# analog_part.net
KiCad netlist of a schematic drawn in Altium Designer
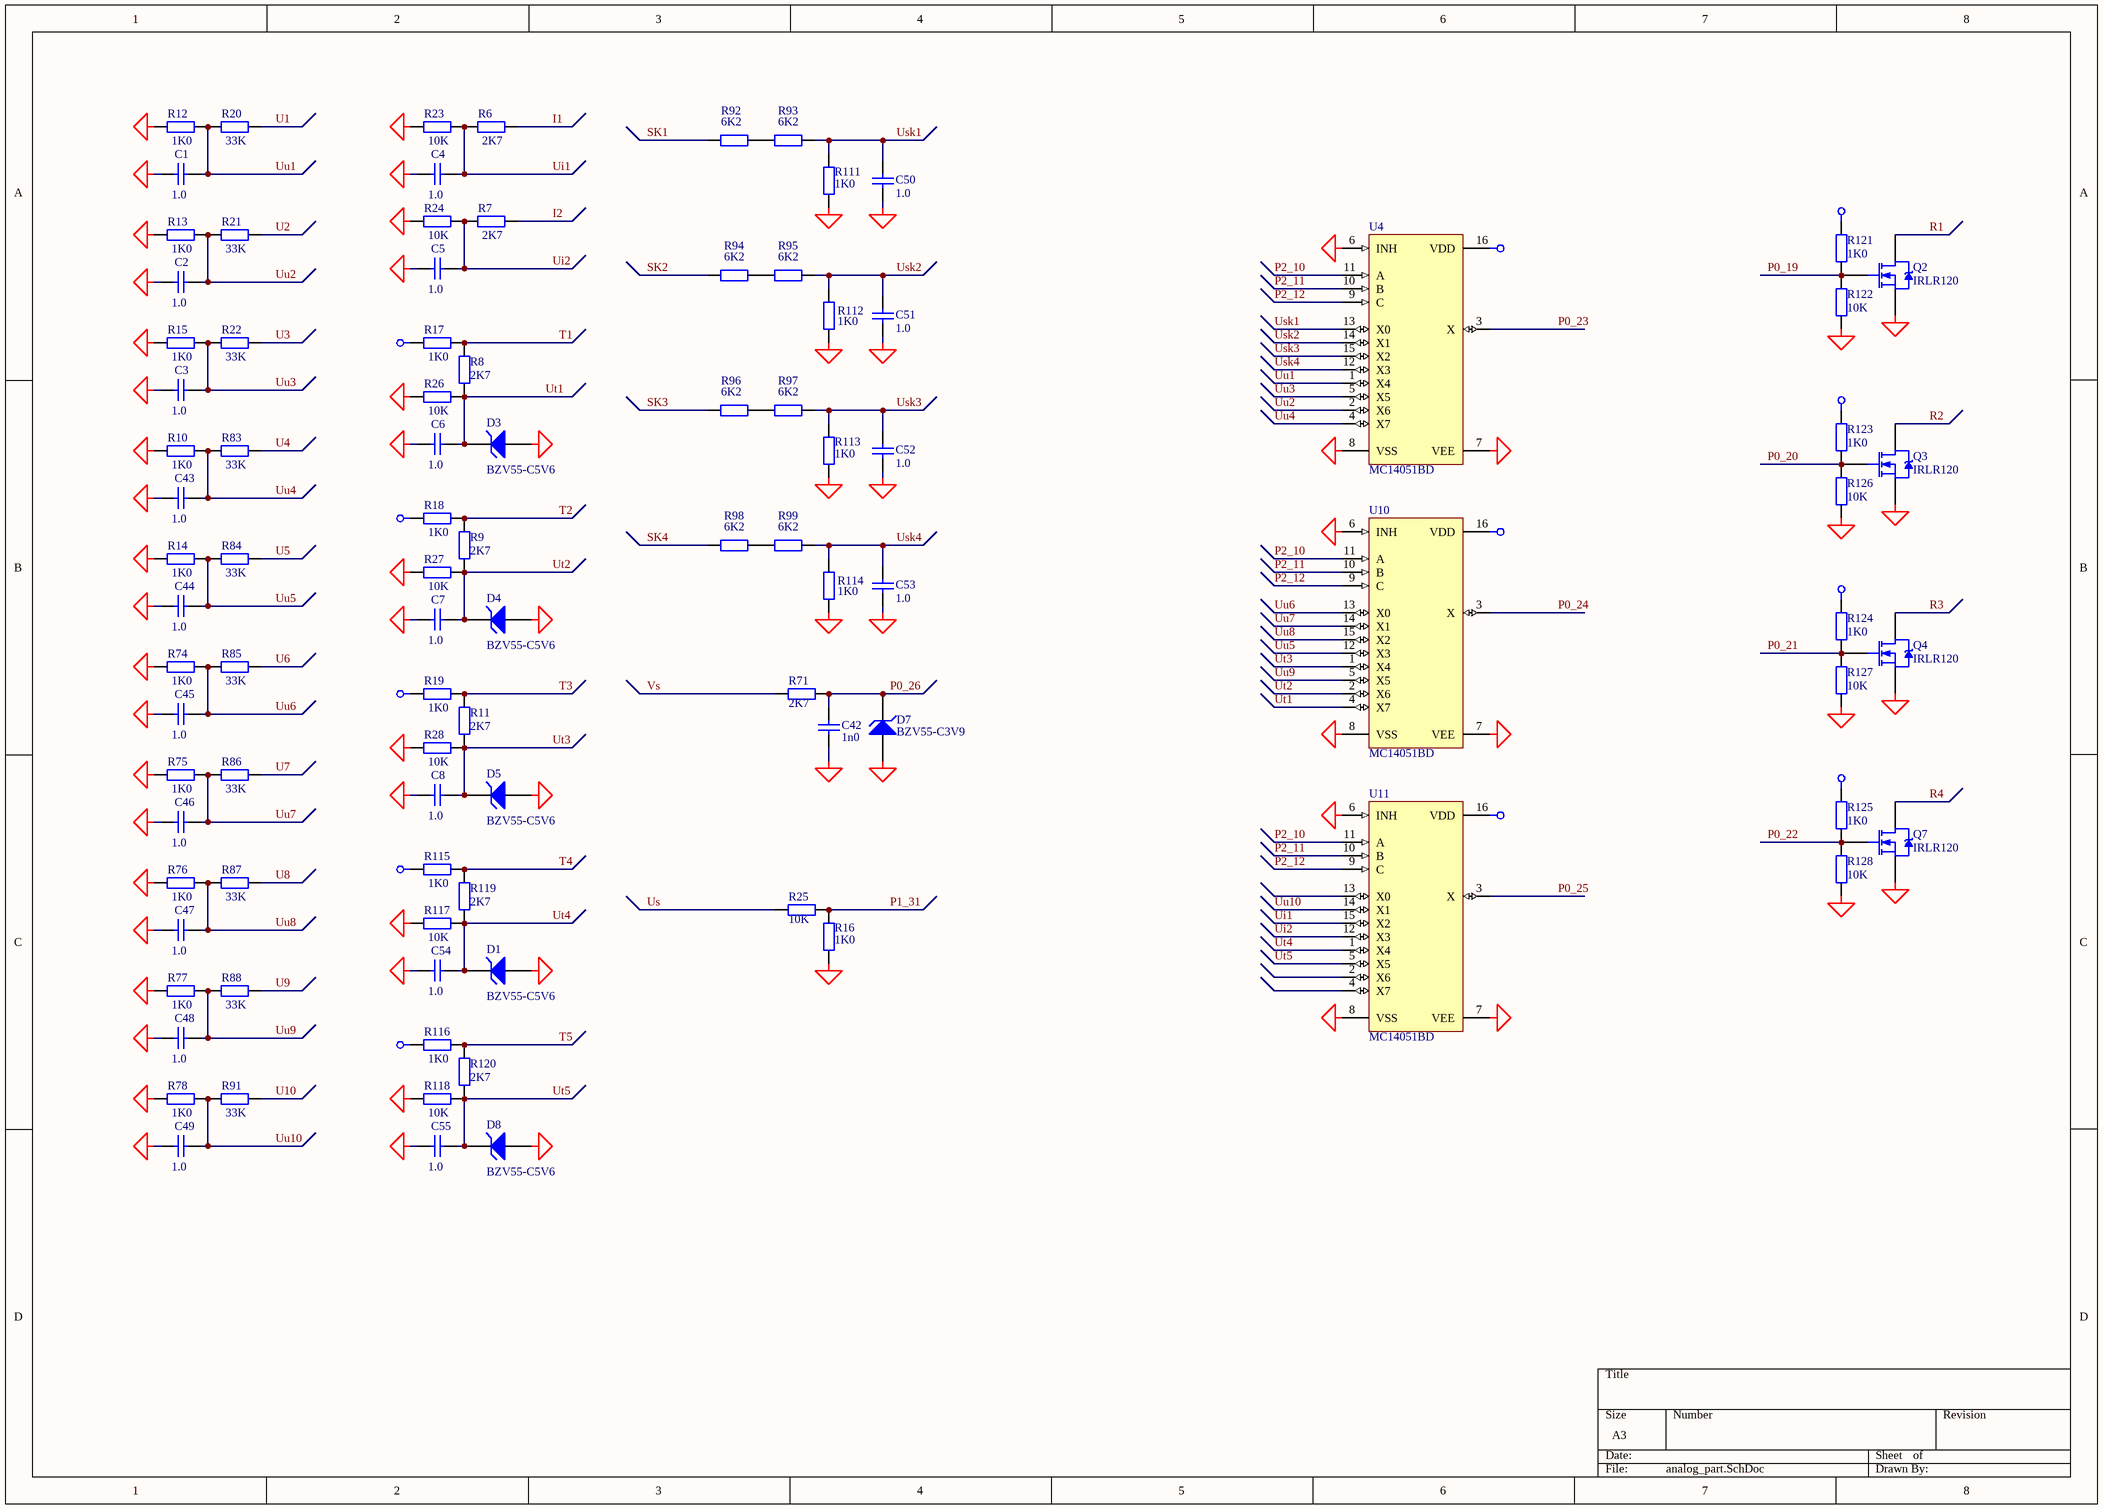
[diagram p0: analog_part.SchDoc]

(export (version "E")
  (design (tool "Eeschema 10.0.6"))
  (components
    (comp (ref "C1")
      (value "1.0")
      (footprint "C3216-1206")
      (description "Capacitor (Semiconductor SIM Model)")
      (fields (field (name "MANUFACTURER") "Generic Components") (field (name "PUBLISHER") "Altium Limited"))
      (libsource (lib "Miscellaneous Devices") (part "Cap Semi"))
    )
    (comp (ref "C2")
      (value "1.0")
      (footprint "C3216-1206")
      (description "Capacitor (Semiconductor SIM Model)")
      (fields (field (name "MANUFACTURER") "Generic Components") (field (name "PUBLISHER") "Altium Limited"))
      (libsource (lib "Miscellaneous Devices") (part "Cap Semi"))
    )
    (comp (ref "C3")
      (value "1.0")
      (footprint "C3216-1206")
      (description "Capacitor (Semiconductor SIM Model)")
      (fields (field (name "MANUFACTURER") "Generic Components") (field (name "PUBLISHER") "Altium Limited"))
      (libsource (lib "Miscellaneous Devices") (part "Cap Semi"))
    )
    (comp (ref "C4")
      (value "1.0")
      (footprint "C3216-1206")
      (description "Capacitor (Semiconductor SIM Model)")
      (fields (field (name "MANUFACTURER") "Generic Components") (field (name "PUBLISHER") "Altium Limited"))
      (libsource (lib "Miscellaneous Devices") (part "Cap Semi"))
    )
    (comp (ref "C5")
      (value "1.0")
      (footprint "C3216-1206")
      (description "Capacitor (Semiconductor SIM Model)")
      (fields (field (name "MANUFACTURER") "Generic Components") (field (name "PUBLISHER") "Altium Limited"))
      (libsource (lib "Miscellaneous Devices") (part "Cap Semi"))
    )
    (comp (ref "C6")
      (value "1.0")
      (footprint "C3216-1206")
      (description "Capacitor (Semiconductor SIM Model)")
      (fields (field (name "MANUFACTURER") "Generic Components") (field (name "PUBLISHER") "Altium Limited"))
      (libsource (lib "Miscellaneous Devices") (part "Cap Semi"))
    )
    (comp (ref "C7")
      (value "1.0")
      (footprint "C3216-1206")
      (description "Capacitor (Semiconductor SIM Model)")
      (fields (field (name "MANUFACTURER") "Generic Components") (field (name "PUBLISHER") "Altium Limited"))
      (libsource (lib "Miscellaneous Devices") (part "Cap Semi"))
    )
    (comp (ref "C8")
      (value "1.0")
      (footprint "_1206")
      (description "Capacitor (Semiconductor SIM Model)")
      (fields (field (name "MANUFACTURER") "Generic Components") (field (name "PUBLISHER") "Altium Limited"))
      (libsource (lib "Miscellaneous Devices") (part "Cap Semi"))
    )
    (comp (ref "C42")
      (value "1n0")
      (footprint "_1206")
      (description "Capacitor (Semiconductor SIM Model)")
      (fields (field (name "MANUFACTURER") "Generic Components") (field (name "PUBLISHER") "Altium Limited"))
      (libsource (lib "") (part "Cap Semi_1"))
    )
    (comp (ref "C43")
      (value "1.0")
      (footprint "C3216-1206")
      (description "Capacitor (Semiconductor SIM Model)")
      (fields (field (name "MANUFACTURER") "Generic Components") (field (name "PUBLISHER") "Altium Limited"))
      (libsource (lib "Miscellaneous Devices") (part "Cap Semi"))
    )
    (comp (ref "C44")
      (value "1.0")
      (footprint "C3216-1206")
      (description "Capacitor (Semiconductor SIM Model)")
      (fields (field (name "MANUFACTURER") "Generic Components") (field (name "PUBLISHER") "Altium Limited"))
      (libsource (lib "Miscellaneous Devices") (part "Cap Semi"))
    )
    (comp (ref "C45")
      (value "1.0")
      (footprint "C3216-1206")
      (description "Capacitor (Semiconductor SIM Model)")
      (fields (field (name "MANUFACTURER") "Generic Components") (field (name "PUBLISHER") "Altium Limited"))
      (libsource (lib "Miscellaneous Devices") (part "Cap Semi"))
    )
    (comp (ref "C46")
      (value "1.0")
      (footprint "C3216-1206")
      (description "Capacitor (Semiconductor SIM Model)")
      (fields (field (name "MANUFACTURER") "Generic Components") (field (name "PUBLISHER") "Altium Limited"))
      (libsource (lib "Miscellaneous Devices") (part "Cap Semi"))
    )
    (comp (ref "C47")
      (value "1.0")
      (footprint "C3216-1206")
      (description "Capacitor (Semiconductor SIM Model)")
      (fields (field (name "MANUFACTURER") "Generic Components") (field (name "PUBLISHER") "Altium Limited"))
      (libsource (lib "Miscellaneous Devices") (part "Cap Semi"))
    )
    (comp (ref "C48")
      (value "1.0")
      (footprint "C3216-1206")
      (description "Capacitor (Semiconductor SIM Model)")
      (fields (field (name "MANUFACTURER") "Generic Components") (field (name "PUBLISHER") "Altium Limited"))
      (libsource (lib "Miscellaneous Devices") (part "Cap Semi"))
    )
    (comp (ref "C49")
      (value "1.0")
      (footprint "C3216-1206")
      (description "Capacitor (Semiconductor SIM Model)")
      (fields (field (name "MANUFACTURER") "Generic Components") (field (name "PUBLISHER") "Altium Limited"))
      (libsource (lib "Miscellaneous Devices") (part "Cap Semi"))
    )
    (comp (ref "C50")
      (value "1.0")
      (footprint "C3216-1206")
      (description "Capacitor (Semiconductor SIM Model)")
      (fields (field (name "MANUFACTURER") "Generic Components") (field (name "PUBLISHER") "Altium Limited"))
      (libsource (lib "Miscellaneous Devices") (part "Cap Semi"))
    )
    (comp (ref "C51")
      (value "1.0")
      (footprint "C3216-1206")
      (description "Capacitor (Semiconductor SIM Model)")
      (fields (field (name "MANUFACTURER") "Generic Components") (field (name "PUBLISHER") "Altium Limited"))
      (libsource (lib "Miscellaneous Devices") (part "Cap Semi"))
    )
    (comp (ref "C52")
      (value "1.0")
      (footprint "C3216-1206")
      (description "Capacitor (Semiconductor SIM Model)")
      (fields (field (name "MANUFACTURER") "Generic Components") (field (name "PUBLISHER") "Altium Limited"))
      (libsource (lib "Miscellaneous Devices") (part "Cap Semi"))
    )
    (comp (ref "C53")
      (value "1.0")
      (footprint "C3216-1206")
      (description "Capacitor (Semiconductor SIM Model)")
      (fields (field (name "MANUFACTURER") "Generic Components") (field (name "PUBLISHER") "Altium Limited"))
      (libsource (lib "Miscellaneous Devices") (part "Cap Semi"))
    )
    (comp (ref "C54")
      (value "1.0")
      (footprint "_1206")
      (description "Capacitor (Semiconductor SIM Model)")
      (fields (field (name "MANUFACTURER") "Generic Components") (field (name "PUBLISHER") "Altium Limited"))
      (libsource (lib "Miscellaneous Devices") (part "Cap Semi"))
    )
    (comp (ref "C55")
      (value "1.0")
      (footprint "_1206")
      (description "Capacitor (Semiconductor SIM Model)")
      (fields (field (name "MANUFACTURER") "Generic Components") (field (name "PUBLISHER") "Altium Limited"))
      (libsource (lib "Miscellaneous Devices") (part "Cap Semi"))
    )
    (comp (ref "D1")
      (value "BZV55-C5V6")
      (footprint "_1206d")
      (description "Zener Diode")
      (fields (field (name "MANUFACTURER") "Generic Components") (field (name "PUBLISHER") "Altium Limited"))
      (libsource (lib "Miscellaneous Devices") (part "D Zener"))
    )
    (comp (ref "D3")
      (value "BZV55-C5V6")
      (footprint "_1206d")
      (description "Zener Diode")
      (fields (field (name "MANUFACTURER") "Generic Components") (field (name "PUBLISHER") "Altium Limited"))
      (libsource (lib "Miscellaneous Devices") (part "D Zener"))
    )
    (comp (ref "D4")
      (value "BZV55-C5V6")
      (footprint "_1206d")
      (description "Zener Diode")
      (fields (field (name "MANUFACTURER") "Generic Components") (field (name "PUBLISHER") "Altium Limited"))
      (libsource (lib "Miscellaneous Devices") (part "D Zener"))
    )
    (comp (ref "D5")
      (value "BZV55-C5V6")
      (footprint "_1206d")
      (description "Zener Diode")
      (fields (field (name "MANUFACTURER") "Generic Components") (field (name "PUBLISHER") "Altium Limited"))
      (libsource (lib "Miscellaneous Devices") (part "D Zener"))
    )
    (comp (ref "D7")
      (value "BZV55-C3V9")
      (footprint "_1206d")
      (description "Zener Diode")
      (fields (field (name "MANUFACTURER") "Generic Components") (field (name "PUBLISHER") "Altium Limited"))
      (libsource (lib "") (part "D Zener_1"))
    )
    (comp (ref "D8")
      (value "BZV55-C5V6")
      (footprint "_1206d")
      (description "Zener Diode")
      (fields (field (name "MANUFACTURER") "Generic Components") (field (name "PUBLISHER") "Altium Limited"))
      (libsource (lib "Miscellaneous Devices") (part "D Zener"))
    )
    (comp (ref "Q2")
      (value "IRLR120")
      (footprint "SIP-G3/E8")
      (description "HEXFET N-Channel Power MOSFET")
      (fields
        (field (name "MANUFACTURER") "International Rectifier")
        (field (name "PUBLISHER") "Altium Limited")
      )
      (libsource (lib "IR Discrete MOSFET") (part "IRFR120"))
    )
    (comp (ref "Q3")
      (value "IRLR120")
      (footprint "SIP-G3/E8")
      (description "HEXFET N-Channel Power MOSFET")
      (fields
        (field (name "MANUFACTURER") "International Rectifier")
        (field (name "PUBLISHER") "Altium Limited")
      )
      (libsource (lib "IR Discrete MOSFET") (part "IRFR120"))
    )
    (comp (ref "Q4")
      (value "IRLR120")
      (footprint "SIP-G3/E8")
      (description "HEXFET N-Channel Power MOSFET")
      (fields
        (field (name "MANUFACTURER") "International Rectifier")
        (field (name "PUBLISHER") "Altium Limited")
      )
      (libsource (lib "IR Discrete MOSFET") (part "IRFR120"))
    )
    (comp (ref "Q7")
      (value "IRLR120")
      (footprint "SIP-G3/E8")
      (description "HEXFET N-Channel Power MOSFET")
      (fields
        (field (name "MANUFACTURER") "International Rectifier")
        (field (name "PUBLISHER") "Altium Limited")
      )
      (libsource (lib "IR Discrete MOSFET") (part "IRFR120"))
    )
    (comp (ref "R6")
      (value "2K7")
      (footprint "_1206")
      (description "Resistor")
      (fields (field (name "MANUFACTURER") "Generic Components") (field (name "PUBLISHER") "Altium Limited"))
      (libsource (lib "Miscellaneous Devices") (part "Res2"))
    )
    (comp (ref "R7")
      (value "2K7")
      (footprint "_1206")
      (description "Resistor")
      (fields (field (name "MANUFACTURER") "Generic Components") (field (name "PUBLISHER") "Altium Limited"))
      (libsource (lib "Miscellaneous Devices") (part "Res2"))
    )
    (comp (ref "R8")
      (value "2K7")
      (footprint "_1206")
      (description "Resistor")
      (fields (field (name "MANUFACTURER") "Generic Components") (field (name "PUBLISHER") "Altium Limited"))
      (libsource (lib "") (part "Res2_2"))
    )
    (comp (ref "R9")
      (value "2K7")
      (footprint "_1206")
      (description "Resistor")
      (fields (field (name "MANUFACTURER") "Generic Components") (field (name "PUBLISHER") "Altium Limited"))
      (libsource (lib "") (part "Res2_2"))
    )
    (comp (ref "R10")
      (value "1K0")
      (footprint "_1206")
      (description "Resistor")
      (fields (field (name "MANUFACTURER") "Generic Components") (field (name "PUBLISHER") "Altium Limited"))
      (libsource (lib "") (part "Res2_1"))
    )
    (comp (ref "R11")
      (value "2K7")
      (footprint "_1206")
      (description "Resistor")
      (fields (field (name "MANUFACTURER") "Generic Components") (field (name "PUBLISHER") "Altium Limited"))
      (libsource (lib "") (part "Res2_2"))
    )
    (comp (ref "R12")
      (value "1K0")
      (footprint "_1206")
      (description "Resistor")
      (fields (field (name "MANUFACTURER") "Generic Components") (field (name "PUBLISHER") "Altium Limited"))
      (libsource (lib "") (part "Res2_1"))
    )
    (comp (ref "R13")
      (value "1K0")
      (footprint "_1206")
      (description "Resistor")
      (fields (field (name "MANUFACTURER") "Generic Components") (field (name "PUBLISHER") "Altium Limited"))
      (libsource (lib "") (part "Res2_1"))
    )
    (comp (ref "R14")
      (value "1K0")
      (footprint "_1206")
      (description "Resistor")
      (fields (field (name "MANUFACTURER") "Generic Components") (field (name "PUBLISHER") "Altium Limited"))
      (libsource (lib "") (part "Res2_1"))
    )
    (comp (ref "R15")
      (value "1K0")
      (footprint "_1206")
      (description "Resistor")
      (fields (field (name "MANUFACTURER") "Generic Components") (field (name "PUBLISHER") "Altium Limited"))
      (libsource (lib "") (part "Res2_1"))
    )
    (comp (ref "R16")
      (value "1K0")
      (footprint "_1206")
      (description "Resistor")
      (fields (field (name "MANUFACTURER") "Generic Components") (field (name "PUBLISHER") "Altium Limited"))
      (libsource (lib "") (part "Res2_3"))
    )
    (comp (ref "R17")
      (value "1K0")
      (footprint "_1206")
      (description "Resistor")
      (fields (field (name "MANUFACTURER") "Generic Components") (field (name "PUBLISHER") "Altium Limited"))
      (libsource (lib "") (part "Res2_1"))
    )
    (comp (ref "R18")
      (value "1K0")
      (footprint "_1206")
      (description "Resistor")
      (fields (field (name "MANUFACTURER") "Generic Components") (field (name "PUBLISHER") "Altium Limited"))
      (libsource (lib "") (part "Res2_1"))
    )
    (comp (ref "R19")
      (value "1K0")
      (footprint "_1206")
      (description "Resistor")
      (fields (field (name "MANUFACTURER") "Generic Components") (field (name "PUBLISHER") "Altium Limited"))
      (libsource (lib "") (part "Res2_1"))
    )
    (comp (ref "R20")
      (value "33K")
      (footprint "_1206")
      (description "Resistor")
      (fields (field (name "MANUFACTURER") "Generic Components") (field (name "PUBLISHER") "Altium Limited"))
      (libsource (lib "Miscellaneous Devices") (part "Res2"))
    )
    (comp (ref "R21")
      (value "33K")
      (footprint "_1206")
      (description "Resistor")
      (fields (field (name "MANUFACTURER") "Generic Components") (field (name "PUBLISHER") "Altium Limited"))
      (libsource (lib "Miscellaneous Devices") (part "Res2"))
    )
    (comp (ref "R22")
      (value "33K")
      (footprint "_1206")
      (description "Resistor")
      (fields (field (name "MANUFACTURER") "Generic Components") (field (name "PUBLISHER") "Altium Limited"))
      (libsource (lib "Miscellaneous Devices") (part "Res2"))
    )
    (comp (ref "R23")
      (value "10K")
      (footprint "_1206")
      (description "Resistor")
      (fields (field (name "MANUFACTURER") "Generic Components") (field (name "PUBLISHER") "Altium Limited"))
      (libsource (lib "Miscellaneous Devices") (part "Res2"))
    )
    (comp (ref "R24")
      (value "10K")
      (footprint "_1206")
      (description "Resistor")
      (fields (field (name "MANUFACTURER") "Generic Components") (field (name "PUBLISHER") "Altium Limited"))
      (libsource (lib "Miscellaneous Devices") (part "Res2"))
    )
    (comp (ref "R25")
      (value "10K")
      (footprint "_1206")
      (description "Resistor")
      (fields (field (name "MANUFACTURER") "Generic Components") (field (name "PUBLISHER") "Altium Limited"))
      (libsource (lib "") (part "Res2_1"))
    )
    (comp (ref "R26")
      (value "10K")
      (footprint "_1206")
      (description "Resistor")
      (fields (field (name "MANUFACTURER") "Generic Components") (field (name "PUBLISHER") "Altium Limited"))
      (libsource (lib "Miscellaneous Devices") (part "Res2"))
    )
    (comp (ref "R27")
      (value "10K")
      (footprint "_1206")
      (description "Resistor")
      (fields (field (name "MANUFACTURER") "Generic Components") (field (name "PUBLISHER") "Altium Limited"))
      (libsource (lib "Miscellaneous Devices") (part "Res2"))
    )
    (comp (ref "R28")
      (value "10K")
      (footprint "_1206")
      (description "Resistor")
      (fields (field (name "MANUFACTURER") "Generic Components") (field (name "PUBLISHER") "Altium Limited"))
      (libsource (lib "Miscellaneous Devices") (part "Res2"))
    )
    (comp (ref "R71")
      (value "2K7")
      (footprint "_1206")
      (description "Resistor")
      (fields (field (name "MANUFACTURER") "Generic Components") (field (name "PUBLISHER") "Altium Limited"))
      (libsource (lib "") (part "Res2_4"))
    )
    (comp (ref "R74")
      (value "1K0")
      (footprint "_1206")
      (description "Resistor")
      (fields (field (name "MANUFACTURER") "Generic Components") (field (name "PUBLISHER") "Altium Limited"))
      (libsource (lib "") (part "Res2_1"))
    )
    (comp (ref "R75")
      (value "1K0")
      (footprint "_1206")
      (description "Resistor")
      (fields (field (name "MANUFACTURER") "Generic Components") (field (name "PUBLISHER") "Altium Limited"))
      (libsource (lib "") (part "Res2_1"))
    )
    (comp (ref "R76")
      (value "1K0")
      (footprint "_1206")
      (description "Resistor")
      (fields (field (name "MANUFACTURER") "Generic Components") (field (name "PUBLISHER") "Altium Limited"))
      (libsource (lib "") (part "Res2_1"))
    )
    (comp (ref "R77")
      (value "1K0")
      (footprint "_1206")
      (description "Resistor")
      (fields (field (name "MANUFACTURER") "Generic Components") (field (name "PUBLISHER") "Altium Limited"))
      (libsource (lib "") (part "Res2_1"))
    )
    (comp (ref "R78")
      (value "1K0")
      (footprint "_1206")
      (description "Resistor")
      (fields (field (name "MANUFACTURER") "Generic Components") (field (name "PUBLISHER") "Altium Limited"))
      (libsource (lib "") (part "Res2_1"))
    )
    (comp (ref "R83")
      (value "33K")
      (footprint "_1206")
      (description "Resistor")
      (fields (field (name "MANUFACTURER") "Generic Components") (field (name "PUBLISHER") "Altium Limited"))
      (libsource (lib "Miscellaneous Devices") (part "Res2"))
    )
    (comp (ref "R84")
      (value "33K")
      (footprint "_1206")
      (description "Resistor")
      (fields (field (name "MANUFACTURER") "Generic Components") (field (name "PUBLISHER") "Altium Limited"))
      (libsource (lib "Miscellaneous Devices") (part "Res2"))
    )
    (comp (ref "R85")
      (value "33K")
      (footprint "_1206")
      (description "Resistor")
      (fields (field (name "MANUFACTURER") "Generic Components") (field (name "PUBLISHER") "Altium Limited"))
      (libsource (lib "Miscellaneous Devices") (part "Res2"))
    )
    (comp (ref "R86")
      (value "33K")
      (footprint "_1206")
      (description "Resistor")
      (fields (field (name "MANUFACTURER") "Generic Components") (field (name "PUBLISHER") "Altium Limited"))
      (libsource (lib "Miscellaneous Devices") (part "Res2"))
    )
    (comp (ref "R87")
      (value "33K")
      (footprint "_1206")
      (description "Resistor")
      (fields (field (name "MANUFACTURER") "Generic Components") (field (name "PUBLISHER") "Altium Limited"))
      (libsource (lib "Miscellaneous Devices") (part "Res2"))
    )
    (comp (ref "R88")
      (value "33K")
      (footprint "_1206")
      (description "Resistor")
      (fields (field (name "MANUFACTURER") "Generic Components") (field (name "PUBLISHER") "Altium Limited"))
      (libsource (lib "Miscellaneous Devices") (part "Res2"))
    )
    (comp (ref "R91")
      (value "33K")
      (footprint "_1206")
      (description "Resistor")
      (fields (field (name "MANUFACTURER") "Generic Components") (field (name "PUBLISHER") "Altium Limited"))
      (libsource (lib "Miscellaneous Devices") (part "Res2"))
    )
    (comp (ref "R92")
      (value "6K2")
      (footprint "_1206")
      (description "Resistor")
      (fields (field (name "MANUFACTURER") "Generic Components") (field (name "PUBLISHER") "Altium Limited"))
      (libsource (lib "Miscellaneous Devices") (part "Res2"))
    )
    (comp (ref "R93")
      (value "6K2")
      (footprint "_1206")
      (description "Resistor")
      (fields (field (name "MANUFACTURER") "Generic Components") (field (name "PUBLISHER") "Altium Limited"))
      (libsource (lib "Miscellaneous Devices") (part "Res2"))
    )
    (comp (ref "R94")
      (value "6K2")
      (footprint "_1206")
      (description "Resistor")
      (fields (field (name "MANUFACTURER") "Generic Components") (field (name "PUBLISHER") "Altium Limited"))
      (libsource (lib "Miscellaneous Devices") (part "Res2"))
    )
    (comp (ref "R95")
      (value "6K2")
      (footprint "_1206")
      (description "Resistor")
      (fields (field (name "MANUFACTURER") "Generic Components") (field (name "PUBLISHER") "Altium Limited"))
      (libsource (lib "Miscellaneous Devices") (part "Res2"))
    )
    (comp (ref "R96")
      (value "6K2")
      (footprint "_1206")
      (description "Resistor")
      (fields (field (name "MANUFACTURER") "Generic Components") (field (name "PUBLISHER") "Altium Limited"))
      (libsource (lib "Miscellaneous Devices") (part "Res2"))
    )
    (comp (ref "R97")
      (value "6K2")
      (footprint "_1206")
      (description "Resistor")
      (fields (field (name "MANUFACTURER") "Generic Components") (field (name "PUBLISHER") "Altium Limited"))
      (libsource (lib "Miscellaneous Devices") (part "Res2"))
    )
    (comp (ref "R98")
      (value "6K2")
      (footprint "_1206")
      (description "Resistor")
      (fields (field (name "MANUFACTURER") "Generic Components") (field (name "PUBLISHER") "Altium Limited"))
      (libsource (lib "Miscellaneous Devices") (part "Res2"))
    )
    (comp (ref "R99")
      (value "6K2")
      (footprint "_1206")
      (description "Resistor")
      (fields (field (name "MANUFACTURER") "Generic Components") (field (name "PUBLISHER") "Altium Limited"))
      (libsource (lib "Miscellaneous Devices") (part "Res2"))
    )
    (comp (ref "R111")
      (value "1K0")
      (footprint "_1206")
      (description "Resistor")
      (fields (field (name "MANUFACTURER") "Generic Components") (field (name "PUBLISHER") "Altium Limited"))
      (libsource (lib "") (part "Res2_2"))
    )
    (comp (ref "R112")
      (value "1K0")
      (footprint "_1206")
      (description "Resistor")
      (fields (field (name "MANUFACTURER") "Generic Components") (field (name "PUBLISHER") "Altium Limited"))
      (libsource (lib "") (part "Res2_2"))
    )
    (comp (ref "R113")
      (value "1K0")
      (footprint "_1206")
      (description "Resistor")
      (fields (field (name "MANUFACTURER") "Generic Components") (field (name "PUBLISHER") "Altium Limited"))
      (libsource (lib "") (part "Res2_2"))
    )
    (comp (ref "R114")
      (value "1K0")
      (footprint "_1206")
      (description "Resistor")
      (fields (field (name "MANUFACTURER") "Generic Components") (field (name "PUBLISHER") "Altium Limited"))
      (libsource (lib "") (part "Res2_2"))
    )
    (comp (ref "R115")
      (value "1K0")
      (footprint "_1206")
      (description "Resistor")
      (fields (field (name "MANUFACTURER") "Generic Components") (field (name "PUBLISHER") "Altium Limited"))
      (libsource (lib "") (part "Res2_1"))
    )
    (comp (ref "R116")
      (value "1K0")
      (footprint "_1206")
      (description "Resistor")
      (fields (field (name "MANUFACTURER") "Generic Components") (field (name "PUBLISHER") "Altium Limited"))
      (libsource (lib "") (part "Res2_1"))
    )
    (comp (ref "R117")
      (value "10K")
      (footprint "_1206")
      (description "Resistor")
      (fields (field (name "MANUFACTURER") "Generic Components") (field (name "PUBLISHER") "Altium Limited"))
      (libsource (lib "Miscellaneous Devices") (part "Res2"))
    )
    (comp (ref "R118")
      (value "10K")
      (footprint "_1206")
      (description "Resistor")
      (fields (field (name "MANUFACTURER") "Generic Components") (field (name "PUBLISHER") "Altium Limited"))
      (libsource (lib "Miscellaneous Devices") (part "Res2"))
    )
    (comp (ref "R119")
      (value "2K7")
      (footprint "_1206")
      (description "Resistor")
      (fields (field (name "MANUFACTURER") "Generic Components") (field (name "PUBLISHER") "Altium Limited"))
      (libsource (lib "") (part "Res2_2"))
    )
    (comp (ref "R120")
      (value "2K7")
      (footprint "_1206")
      (description "Resistor")
      (fields (field (name "MANUFACTURER") "Generic Components") (field (name "PUBLISHER") "Altium Limited"))
      (libsource (lib "") (part "Res2_2"))
    )
    (comp (ref "R121")
      (value "1K0")
      (footprint "_1206")
      (description "Resistor")
      (fields (field (name "MANUFACTURER") "Generic Components") (field (name "PUBLISHER") "Altium Limited"))
      (libsource (lib "") (part "Res2_2"))
    )
    (comp (ref "R122")
      (value "10K")
      (footprint "_1206")
      (description "Resistor")
      (fields (field (name "MANUFACTURER") "Generic Components") (field (name "PUBLISHER") "Altium Limited"))
      (libsource (lib "") (part "Res2_3"))
    )
    (comp (ref "R123")
      (value "1K0")
      (footprint "_1206")
      (description "Resistor")
      (fields (field (name "MANUFACTURER") "Generic Components") (field (name "PUBLISHER") "Altium Limited"))
      (libsource (lib "") (part "Res2_2"))
    )
    (comp (ref "R124")
      (value "1K0")
      (footprint "_1206")
      (description "Resistor")
      (fields (field (name "MANUFACTURER") "Generic Components") (field (name "PUBLISHER") "Altium Limited"))
      (libsource (lib "") (part "Res2_2"))
    )
    (comp (ref "R125")
      (value "1K0")
      (footprint "_1206")
      (description "Resistor")
      (fields (field (name "MANUFACTURER") "Generic Components") (field (name "PUBLISHER") "Altium Limited"))
      (libsource (lib "") (part "Res2_2"))
    )
    (comp (ref "R126")
      (value "10K")
      (footprint "_1206")
      (description "Resistor")
      (fields (field (name "MANUFACTURER") "Generic Components") (field (name "PUBLISHER") "Altium Limited"))
      (libsource (lib "") (part "Res2_3"))
    )
    (comp (ref "R127")
      (value "10K")
      (footprint "_1206")
      (description "Resistor")
      (fields (field (name "MANUFACTURER") "Generic Components") (field (name "PUBLISHER") "Altium Limited"))
      (libsource (lib "") (part "Res2_3"))
    )
    (comp (ref "R128")
      (value "10K")
      (footprint "_1206")
      (description "Resistor")
      (fields (field (name "MANUFACTURER") "Generic Components") (field (name "PUBLISHER") "Altium Limited"))
      (libsource (lib "") (part "Res2_3"))
    )
    (comp (ref "U4")
      (value "MC14051BD")
      (footprint "SO-G16/C5.85")
      (description "8-Channel Analog Multiplexer/Demultiplexer")
      (fields (field (name "MANUFACTURER") "ON Semiconductor") (field (name "PUBLISHER") "Altium Limited"))
      (libsource (lib "ON Semi Logic Multiplexer") (part "MC14051BD"))
    )
    (comp (ref "U10")
      (value "MC14051BD")
      (footprint "SO-G16/C5.85")
      (description "8-Channel Analog Multiplexer/Demultiplexer")
      (fields (field (name "MANUFACTURER") "ON Semiconductor") (field (name "PUBLISHER") "Altium Limited"))
      (libsource (lib "ON Semi Logic Multiplexer") (part "MC14051BD"))
    )
    (comp (ref "U11")
      (value "MC14051BD")
      (footprint "SO-G16/C5.85")
      (description "8-Channel Analog Multiplexer/Demultiplexer")
      (fields (field (name "MANUFACTURER") "ON Semiconductor") (field (name "PUBLISHER") "Altium Limited"))
      (libsource (lib "ON Semi Logic Multiplexer") (part "MC14051BD"))
    )
  )
  (nets
    (net (code "1") (name "+3v3") (class "Default")
      (node (ref "U10") (pin "16") (pinfunction "VDD_16") (pintype "power_in"))
      (node (ref "U11") (pin "16") (pinfunction "VDD_16") (pintype "power_in"))
      (node (ref "U4") (pin "16") (pinfunction "VDD_16") (pintype "power_in"))
    )
    (net (code "2") (name "+5v") (class "Default")
      (node (ref "R115") (pin "2") (pinfunction "2_2") (pintype "passive"))
      (node (ref "R116") (pin "2") (pinfunction "2_2") (pintype "passive"))
      (node (ref "R121") (pin "2") (pinfunction "2_2") (pintype "passive"))
      (node (ref "R123") (pin "2") (pinfunction "2_2") (pintype "passive"))
      (node (ref "R124") (pin "2") (pinfunction "2_2") (pintype "passive"))
      (node (ref "R125") (pin "2") (pinfunction "2_2") (pintype "passive"))
      (node (ref "R17") (pin "2") (pinfunction "2_2") (pintype "passive"))
      (node (ref "R18") (pin "2") (pinfunction "2_2") (pintype "passive"))
      (node (ref "R19") (pin "2") (pinfunction "2_2") (pintype "passive"))
    )
    (net (code "3") (name "/I1") (class "Default")
      (node (ref "R6") (pin "2") (pinfunction "2_2") (pintype "passive"))
    )
    (net (code "4") (name "/I2") (class "Default")
      (node (ref "R7") (pin "2") (pinfunction "2_2") (pintype "passive"))
    )
    (net (code "5") (name "/P0_19") (class "Default")
      (node (ref "Q2") (pin "1") (pinfunction "G_1") (pintype "passive"))
      (node (ref "R121") (pin "1") (pinfunction "1_1") (pintype "passive"))
      (node (ref "R122") (pin "1") (pinfunction "1_1") (pintype "passive"))
    )
    (net (code "6") (name "/P0_20") (class "Default")
      (node (ref "Q3") (pin "1") (pinfunction "G_1") (pintype "passive"))
      (node (ref "R123") (pin "1") (pinfunction "1_1") (pintype "passive"))
      (node (ref "R126") (pin "1") (pinfunction "1_1") (pintype "passive"))
    )
    (net (code "7") (name "/P0_21") (class "Default")
      (node (ref "Q4") (pin "1") (pinfunction "G_1") (pintype "passive"))
      (node (ref "R124") (pin "1") (pinfunction "1_1") (pintype "passive"))
      (node (ref "R127") (pin "1") (pinfunction "1_1") (pintype "passive"))
    )
    (net (code "8") (name "/P0_22") (class "Default")
      (node (ref "Q7") (pin "1") (pinfunction "G_1") (pintype "passive"))
      (node (ref "R125") (pin "1") (pinfunction "1_1") (pintype "passive"))
      (node (ref "R128") (pin "1") (pinfunction "1_1") (pintype "passive"))
    )
    (net (code "9") (name "/P0_23") (class "Default")
      (node (ref "U4") (pin "3") (pinfunction "X_3") (pintype "bidirectional"))
    )
    (net (code "10") (name "/P0_24") (class "Default")
      (node (ref "U10") (pin "3") (pinfunction "X_3") (pintype "bidirectional"))
    )
    (net (code "11") (name "/P0_25") (class "Default")
      (node (ref "U11") (pin "3") (pinfunction "X_3") (pintype "bidirectional"))
    )
    (net (code "12") (name "/P0_26") (class "Default")
      (node (ref "C42") (pin "1") (pinfunction "1_1") (pintype "passive"))
      (node (ref "D7") (pin "2") (pinfunction "K_2") (pintype "passive"))
      (node (ref "R71") (pin "1") (pinfunction "1_1") (pintype "passive"))
    )
    (net (code "13") (name "/P1_31") (class "Default")
      (node (ref "R16") (pin "1") (pinfunction "1_1") (pintype "passive"))
      (node (ref "R25") (pin "1") (pinfunction "1_1") (pintype "passive"))
    )
    (net (code "14") (name "/P2_10") (class "Default")
      (node (ref "U10") (pin "11") (pinfunction "A_11") (pintype "input"))
      (node (ref "U11") (pin "11") (pinfunction "A_11") (pintype "input"))
      (node (ref "U4") (pin "11") (pinfunction "A_11") (pintype "input"))
    )
    (net (code "15") (name "/P2_11") (class "Default")
      (node (ref "U10") (pin "10") (pinfunction "B_10") (pintype "input"))
      (node (ref "U11") (pin "10") (pinfunction "B_10") (pintype "input"))
      (node (ref "U4") (pin "10") (pinfunction "B_10") (pintype "input"))
    )
    (net (code "16") (name "/P2_12") (class "Default")
      (node (ref "U10") (pin "9") (pinfunction "C_9") (pintype "input"))
      (node (ref "U11") (pin "9") (pinfunction "C_9") (pintype "input"))
      (node (ref "U4") (pin "9") (pinfunction "C_9") (pintype "input"))
    )
    (net (code "17") (name "/R1") (class "Default")
      (node (ref "Q2") (pin "4") (pinfunction "D_4") (pintype "passive"))
    )
    (net (code "18") (name "/R2") (class "Default")
      (node (ref "Q3") (pin "4") (pinfunction "D_4") (pintype "passive"))
    )
    (net (code "19") (name "/R3") (class "Default")
      (node (ref "Q4") (pin "4") (pinfunction "D_4") (pintype "passive"))
    )
    (net (code "20") (name "/R4") (class "Default")
      (node (ref "Q7") (pin "4") (pinfunction "D_4") (pintype "passive"))
    )
    (net (code "21") (name "/SK1") (class "Default")
      (node (ref "R92") (pin "1") (pinfunction "1_1") (pintype "passive"))
    )
    (net (code "22") (name "/SK2") (class "Default")
      (node (ref "R94") (pin "1") (pinfunction "1_1") (pintype "passive"))
    )
    (net (code "23") (name "/SK3") (class "Default")
      (node (ref "R96") (pin "1") (pinfunction "1_1") (pintype "passive"))
    )
    (net (code "24") (name "/SK4") (class "Default")
      (node (ref "R98") (pin "1") (pinfunction "1_1") (pintype "passive"))
    )
    (net (code "25") (name "/T1") (class "Default")
      (node (ref "R17") (pin "1") (pinfunction "1_1") (pintype "passive"))
      (node (ref "R8") (pin "2") (pinfunction "2_2") (pintype "passive"))
    )
    (net (code "26") (name "/T2") (class "Default")
      (node (ref "R18") (pin "1") (pinfunction "1_1") (pintype "passive"))
      (node (ref "R9") (pin "2") (pinfunction "2_2") (pintype "passive"))
    )
    (net (code "27") (name "/T3") (class "Default")
      (node (ref "R11") (pin "2") (pinfunction "2_2") (pintype "passive"))
      (node (ref "R19") (pin "1") (pinfunction "1_1") (pintype "passive"))
    )
    (net (code "28") (name "/T4") (class "Default")
      (node (ref "R115") (pin "1") (pinfunction "1_1") (pintype "passive"))
      (node (ref "R119") (pin "2") (pinfunction "2_2") (pintype "passive"))
    )
    (net (code "29") (name "/T5") (class "Default")
      (node (ref "R116") (pin "1") (pinfunction "1_1") (pintype "passive"))
      (node (ref "R120") (pin "2") (pinfunction "2_2") (pintype "passive"))
    )
    (net (code "30") (name "/U1") (class "Default")
      (node (ref "R20") (pin "2") (pinfunction "2_2") (pintype "passive"))
    )
    (net (code "31") (name "/U2") (class "Default")
      (node (ref "R21") (pin "2") (pinfunction "2_2") (pintype "passive"))
    )
    (net (code "32") (name "/U3") (class "Default")
      (node (ref "R22") (pin "2") (pinfunction "2_2") (pintype "passive"))
    )
    (net (code "33") (name "/U4") (class "Default")
      (node (ref "R83") (pin "2") (pinfunction "2_2") (pintype "passive"))
    )
    (net (code "34") (name "/U5") (class "Default")
      (node (ref "R84") (pin "2") (pinfunction "2_2") (pintype "passive"))
    )
    (net (code "35") (name "/U6") (class "Default")
      (node (ref "R85") (pin "2") (pinfunction "2_2") (pintype "passive"))
    )
    (net (code "36") (name "/U7") (class "Default")
      (node (ref "R86") (pin "2") (pinfunction "2_2") (pintype "passive"))
    )
    (net (code "37") (name "/U8") (class "Default")
      (node (ref "R87") (pin "2") (pinfunction "2_2") (pintype "passive"))
    )
    (net (code "38") (name "/U9") (class "Default")
      (node (ref "R88") (pin "2") (pinfunction "2_2") (pintype "passive"))
    )
    (net (code "39") (name "/U10") (class "Default")
      (node (ref "R91") (pin "2") (pinfunction "2_2") (pintype "passive"))
    )
    (net (code "40") (name "/Ui1") (class "Default")
      (node (ref "C4") (pin "1") (pinfunction "1_1") (pintype "passive"))
      (node (ref "R23") (pin "2") (pinfunction "2_2") (pintype "passive"))
      (node (ref "R6") (pin "1") (pinfunction "1_1") (pintype "passive"))
      (node (ref "U11") (pin "15") (pinfunction "X2_15") (pintype "bidirectional"))
    )
    (net (code "41") (name "/Ui2") (class "Default")
      (node (ref "C5") (pin "1") (pinfunction "1_1") (pintype "passive"))
      (node (ref "R24") (pin "2") (pinfunction "2_2") (pintype "passive"))
      (node (ref "R7") (pin "1") (pinfunction "1_1") (pintype "passive"))
      (node (ref "U11") (pin "12") (pinfunction "X3_12") (pintype "bidirectional"))
    )
    (net (code "42") (name "/Us") (class "Default")
      (node (ref "R25") (pin "2") (pinfunction "2_2") (pintype "passive"))
    )
    (net (code "43") (name "/Usk1") (class "Default")
      (node (ref "C50") (pin "1") (pinfunction "1_1") (pintype "passive"))
      (node (ref "R111") (pin "2") (pinfunction "2_2") (pintype "passive"))
      (node (ref "R93") (pin "2") (pinfunction "2_2") (pintype "passive"))
      (node (ref "U4") (pin "13") (pinfunction "X0_13") (pintype "bidirectional"))
    )
    (net (code "44") (name "/Usk2") (class "Default")
      (node (ref "C51") (pin "1") (pinfunction "1_1") (pintype "passive"))
      (node (ref "R112") (pin "2") (pinfunction "2_2") (pintype "passive"))
      (node (ref "R95") (pin "2") (pinfunction "2_2") (pintype "passive"))
      (node (ref "U4") (pin "14") (pinfunction "X1_14") (pintype "bidirectional"))
    )
    (net (code "45") (name "/Usk3") (class "Default")
      (node (ref "C52") (pin "1") (pinfunction "1_1") (pintype "passive"))
      (node (ref "R113") (pin "2") (pinfunction "2_2") (pintype "passive"))
      (node (ref "R97") (pin "2") (pinfunction "2_2") (pintype "passive"))
      (node (ref "U4") (pin "15") (pinfunction "X2_15") (pintype "bidirectional"))
    )
    (net (code "46") (name "/Usk4") (class "Default")
      (node (ref "C53") (pin "1") (pinfunction "1_1") (pintype "passive"))
      (node (ref "R114") (pin "2") (pinfunction "2_2") (pintype "passive"))
      (node (ref "R99") (pin "2") (pinfunction "2_2") (pintype "passive"))
      (node (ref "U4") (pin "12") (pinfunction "X3_12") (pintype "bidirectional"))
    )
    (net (code "47") (name "/Ut1") (class "Default")
      (node (ref "C6") (pin "1") (pinfunction "1_1") (pintype "passive"))
      (node (ref "D3") (pin "2") (pinfunction "K_2") (pintype "passive"))
      (node (ref "R26") (pin "2") (pinfunction "2_2") (pintype "passive"))
      (node (ref "R8") (pin "1") (pinfunction "1_1") (pintype "passive"))
      (node (ref "U10") (pin "4") (pinfunction "X7_4") (pintype "bidirectional"))
    )
    (net (code "48") (name "/Ut2") (class "Default")
      (node (ref "C7") (pin "1") (pinfunction "1_1") (pintype "passive"))
      (node (ref "D4") (pin "2") (pinfunction "K_2") (pintype "passive"))
      (node (ref "R27") (pin "2") (pinfunction "2_2") (pintype "passive"))
      (node (ref "R9") (pin "1") (pinfunction "1_1") (pintype "passive"))
      (node (ref "U10") (pin "2") (pinfunction "X6_2") (pintype "bidirectional"))
    )
    (net (code "49") (name "/Ut3") (class "Default")
      (node (ref "C8") (pin "1") (pinfunction "1_1") (pintype "passive"))
      (node (ref "D5") (pin "2") (pinfunction "K_2") (pintype "passive"))
      (node (ref "R11") (pin "1") (pinfunction "1_1") (pintype "passive"))
      (node (ref "R28") (pin "2") (pinfunction "2_2") (pintype "passive"))
      (node (ref "U10") (pin "1") (pinfunction "X4_1") (pintype "bidirectional"))
    )
    (net (code "50") (name "/Ut4") (class "Default")
      (node (ref "C54") (pin "1") (pinfunction "1_1") (pintype "passive"))
      (node (ref "D1") (pin "2") (pinfunction "K_2") (pintype "passive"))
      (node (ref "R117") (pin "2") (pinfunction "2_2") (pintype "passive"))
      (node (ref "R119") (pin "1") (pinfunction "1_1") (pintype "passive"))
      (node (ref "U11") (pin "1") (pinfunction "X4_1") (pintype "bidirectional"))
    )
    (net (code "51") (name "/Ut5") (class "Default")
      (node (ref "C55") (pin "1") (pinfunction "1_1") (pintype "passive"))
      (node (ref "D8") (pin "2") (pinfunction "K_2") (pintype "passive"))
      (node (ref "R118") (pin "2") (pinfunction "2_2") (pintype "passive"))
      (node (ref "R120") (pin "1") (pinfunction "1_1") (pintype "passive"))
      (node (ref "U11") (pin "5") (pinfunction "X5_5") (pintype "bidirectional"))
    )
    (net (code "52") (name "/Uu1") (class "Default")
      (node (ref "C1") (pin "1") (pinfunction "1_1") (pintype "passive"))
      (node (ref "R12") (pin "1") (pinfunction "1_1") (pintype "passive"))
      (node (ref "R20") (pin "1") (pinfunction "1_1") (pintype "passive"))
      (node (ref "U4") (pin "1") (pinfunction "X4_1") (pintype "bidirectional"))
    )
    (net (code "53") (name "/Uu2") (class "Default")
      (node (ref "C2") (pin "1") (pinfunction "1_1") (pintype "passive"))
      (node (ref "R13") (pin "1") (pinfunction "1_1") (pintype "passive"))
      (node (ref "R21") (pin "1") (pinfunction "1_1") (pintype "passive"))
      (node (ref "U4") (pin "2") (pinfunction "X6_2") (pintype "bidirectional"))
    )
    (net (code "54") (name "/Uu3") (class "Default")
      (node (ref "C3") (pin "1") (pinfunction "1_1") (pintype "passive"))
      (node (ref "R15") (pin "1") (pinfunction "1_1") (pintype "passive"))
      (node (ref "R22") (pin "1") (pinfunction "1_1") (pintype "passive"))
      (node (ref "U4") (pin "5") (pinfunction "X5_5") (pintype "bidirectional"))
    )
    (net (code "55") (name "/Uu4") (class "Default")
      (node (ref "C43") (pin "1") (pinfunction "1_1") (pintype "passive"))
      (node (ref "R10") (pin "1") (pinfunction "1_1") (pintype "passive"))
      (node (ref "R83") (pin "1") (pinfunction "1_1") (pintype "passive"))
      (node (ref "U4") (pin "4") (pinfunction "X7_4") (pintype "bidirectional"))
    )
    (net (code "56") (name "/Uu5") (class "Default")
      (node (ref "C44") (pin "1") (pinfunction "1_1") (pintype "passive"))
      (node (ref "R14") (pin "1") (pinfunction "1_1") (pintype "passive"))
      (node (ref "R84") (pin "1") (pinfunction "1_1") (pintype "passive"))
      (node (ref "U10") (pin "12") (pinfunction "X3_12") (pintype "bidirectional"))
    )
    (net (code "57") (name "/Uu6") (class "Default")
      (node (ref "C45") (pin "1") (pinfunction "1_1") (pintype "passive"))
      (node (ref "R74") (pin "1") (pinfunction "1_1") (pintype "passive"))
      (node (ref "R85") (pin "1") (pinfunction "1_1") (pintype "passive"))
      (node (ref "U10") (pin "13") (pinfunction "X0_13") (pintype "bidirectional"))
    )
    (net (code "58") (name "/Uu7") (class "Default")
      (node (ref "C46") (pin "1") (pinfunction "1_1") (pintype "passive"))
      (node (ref "R75") (pin "1") (pinfunction "1_1") (pintype "passive"))
      (node (ref "R86") (pin "1") (pinfunction "1_1") (pintype "passive"))
      (node (ref "U10") (pin "14") (pinfunction "X1_14") (pintype "bidirectional"))
    )
    (net (code "59") (name "/Uu8") (class "Default")
      (node (ref "C47") (pin "1") (pinfunction "1_1") (pintype "passive"))
      (node (ref "R76") (pin "1") (pinfunction "1_1") (pintype "passive"))
      (node (ref "R87") (pin "1") (pinfunction "1_1") (pintype "passive"))
      (node (ref "U10") (pin "15") (pinfunction "X2_15") (pintype "bidirectional"))
    )
    (net (code "60") (name "/Uu9") (class "Default")
      (node (ref "C48") (pin "1") (pinfunction "1_1") (pintype "passive"))
      (node (ref "R77") (pin "1") (pinfunction "1_1") (pintype "passive"))
      (node (ref "R88") (pin "1") (pinfunction "1_1") (pintype "passive"))
      (node (ref "U10") (pin "5") (pinfunction "X5_5") (pintype "bidirectional"))
    )
    (net (code "61") (name "/Uu10") (class "Default")
      (node (ref "C49") (pin "1") (pinfunction "1_1") (pintype "passive"))
      (node (ref "R78") (pin "1") (pinfunction "1_1") (pintype "passive"))
      (node (ref "R91") (pin "1") (pinfunction "1_1") (pintype "passive"))
      (node (ref "U11") (pin "14") (pinfunction "X1_14") (pintype "bidirectional"))
    )
    (net (code "62") (name "/Vs") (class "Default")
      (node (ref "R71") (pin "2") (pinfunction "2_2") (pintype "passive"))
    )
    (net (code "63") (name "GND") (class "Default")
      (node (ref "C1") (pin "2") (pinfunction "2_2") (pintype "passive"))
      (node (ref "C2") (pin "2") (pinfunction "2_2") (pintype "passive"))
      (node (ref "C3") (pin "2") (pinfunction "2_2") (pintype "passive"))
      (node (ref "C4") (pin "2") (pinfunction "2_2") (pintype "passive"))
      (node (ref "C42") (pin "2") (pinfunction "2_2") (pintype "passive"))
      (node (ref "C43") (pin "2") (pinfunction "2_2") (pintype "passive"))
      (node (ref "C44") (pin "2") (pinfunction "2_2") (pintype "passive"))
      (node (ref "C45") (pin "2") (pinfunction "2_2") (pintype "passive"))
      (node (ref "C46") (pin "2") (pinfunction "2_2") (pintype "passive"))
      (node (ref "C47") (pin "2") (pinfunction "2_2") (pintype "passive"))
      (node (ref "C48") (pin "2") (pinfunction "2_2") (pintype "passive"))
      (node (ref "C49") (pin "2") (pinfunction "2_2") (pintype "passive"))
      (node (ref "C5") (pin "2") (pinfunction "2_2") (pintype "passive"))
      (node (ref "C50") (pin "2") (pinfunction "2_2") (pintype "passive"))
      (node (ref "C51") (pin "2") (pinfunction "2_2") (pintype "passive"))
      (node (ref "C52") (pin "2") (pinfunction "2_2") (pintype "passive"))
      (node (ref "C53") (pin "2") (pinfunction "2_2") (pintype "passive"))
      (node (ref "C54") (pin "2") (pinfunction "2_2") (pintype "passive"))
      (node (ref "C55") (pin "2") (pinfunction "2_2") (pintype "passive"))
      (node (ref "C6") (pin "2") (pinfunction "2_2") (pintype "passive"))
      (node (ref "C7") (pin "2") (pinfunction "2_2") (pintype "passive"))
      (node (ref "C8") (pin "2") (pinfunction "2_2") (pintype "passive"))
      (node (ref "D1") (pin "1") (pinfunction "A_1") (pintype "passive"))
      (node (ref "D3") (pin "1") (pinfunction "A_1") (pintype "passive"))
      (node (ref "D4") (pin "1") (pinfunction "A_1") (pintype "passive"))
      (node (ref "D5") (pin "1") (pinfunction "A_1") (pintype "passive"))
      (node (ref "D7") (pin "1") (pinfunction "A_1") (pintype "passive"))
      (node (ref "D8") (pin "1") (pinfunction "A_1") (pintype "passive"))
      (node (ref "Q2") (pin "3") (pinfunction "S_3") (pintype "passive"))
      (node (ref "Q3") (pin "3") (pinfunction "S_3") (pintype "passive"))
      (node (ref "Q4") (pin "3") (pinfunction "S_3") (pintype "passive"))
      (node (ref "Q7") (pin "3") (pinfunction "S_3") (pintype "passive"))
      (node (ref "R10") (pin "2") (pinfunction "2_2") (pintype "passive"))
      (node (ref "R111") (pin "1") (pinfunction "1_1") (pintype "passive"))
      (node (ref "R112") (pin "1") (pinfunction "1_1") (pintype "passive"))
      (node (ref "R113") (pin "1") (pinfunction "1_1") (pintype "passive"))
      (node (ref "R114") (pin "1") (pinfunction "1_1") (pintype "passive"))
      (node (ref "R117") (pin "1") (pinfunction "1_1") (pintype "passive"))
      (node (ref "R118") (pin "1") (pinfunction "1_1") (pintype "passive"))
      (node (ref "R12") (pin "2") (pinfunction "2_2") (pintype "passive"))
      (node (ref "R122") (pin "2") (pinfunction "2_2") (pintype "passive"))
      (node (ref "R126") (pin "2") (pinfunction "2_2") (pintype "passive"))
      (node (ref "R127") (pin "2") (pinfunction "2_2") (pintype "passive"))
      (node (ref "R128") (pin "2") (pinfunction "2_2") (pintype "passive"))
      (node (ref "R13") (pin "2") (pinfunction "2_2") (pintype "passive"))
      (node (ref "R14") (pin "2") (pinfunction "2_2") (pintype "passive"))
      (node (ref "R15") (pin "2") (pinfunction "2_2") (pintype "passive"))
      (node (ref "R16") (pin "2") (pinfunction "2_2") (pintype "passive"))
      (node (ref "R23") (pin "1") (pinfunction "1_1") (pintype "passive"))
      (node (ref "R24") (pin "1") (pinfunction "1_1") (pintype "passive"))
      (node (ref "R26") (pin "1") (pinfunction "1_1") (pintype "passive"))
      (node (ref "R27") (pin "1") (pinfunction "1_1") (pintype "passive"))
      (node (ref "R28") (pin "1") (pinfunction "1_1") (pintype "passive"))
      (node (ref "R74") (pin "2") (pinfunction "2_2") (pintype "passive"))
      (node (ref "R75") (pin "2") (pinfunction "2_2") (pintype "passive"))
      (node (ref "R76") (pin "2") (pinfunction "2_2") (pintype "passive"))
      (node (ref "R77") (pin "2") (pinfunction "2_2") (pintype "passive"))
      (node (ref "R78") (pin "2") (pinfunction "2_2") (pintype "passive"))
      (node (ref "U10") (pin "6") (pinfunction "INH_6") (pintype "input"))
      (node (ref "U10") (pin "7") (pinfunction "VEE_7") (pintype "power_in"))
      (node (ref "U10") (pin "8") (pinfunction "VSS_8") (pintype "power_in"))
      (node (ref "U11") (pin "6") (pinfunction "INH_6") (pintype "input"))
      (node (ref "U11") (pin "7") (pinfunction "VEE_7") (pintype "power_in"))
      (node (ref "U11") (pin "8") (pinfunction "VSS_8") (pintype "power_in"))
      (node (ref "U4") (pin "6") (pinfunction "INH_6") (pintype "input"))
      (node (ref "U4") (pin "7") (pinfunction "VEE_7") (pintype "power_in"))
      (node (ref "U4") (pin "8") (pinfunction "VSS_8") (pintype "power_in"))
    )
    (net (code "64") (name "Net-(R92-Pad2)") (class "Default")
      (node (ref "R92") (pin "2") (pinfunction "2_2") (pintype "passive"))
      (node (ref "R93") (pin "1") (pinfunction "1_1") (pintype "passive"))
    )
    (net (code "65") (name "Net-(R94-Pad2)") (class "Default")
      (node (ref "R94") (pin "2") (pinfunction "2_2") (pintype "passive"))
      (node (ref "R95") (pin "1") (pinfunction "1_1") (pintype "passive"))
    )
    (net (code "66") (name "Net-(R96-Pad2)") (class "Default")
      (node (ref "R96") (pin "2") (pinfunction "2_2") (pintype "passive"))
      (node (ref "R97") (pin "1") (pinfunction "1_1") (pintype "passive"))
    )
    (net (code "67") (name "Net-(R98-Pad2)") (class "Default")
      (node (ref "R98") (pin "2") (pinfunction "2_2") (pintype "passive"))
      (node (ref "R99") (pin "1") (pinfunction "1_1") (pintype "passive"))
    )
    (net (code "68") (name "unconnected-(U11-X0-Pad13)") (class "Default")
      (node (ref "U11") (pin "13") (pinfunction "X0_13") (pintype "bidirectional"))
    )
    (net (code "69") (name "unconnected-(U11-X6-Pad2)") (class "Default")
      (node (ref "U11") (pin "2") (pinfunction "X6_2") (pintype "bidirectional"))
    )
    (net (code "70") (name "unconnected-(U11-X7-Pad4)") (class "Default")
      (node (ref "U11") (pin "4") (pinfunction "X7_4") (pintype "bidirectional"))
    )
  )
)
